# Ampli_FI_10_7MHz.net
KiCad netlist of a schematic drawn in Altium Designer
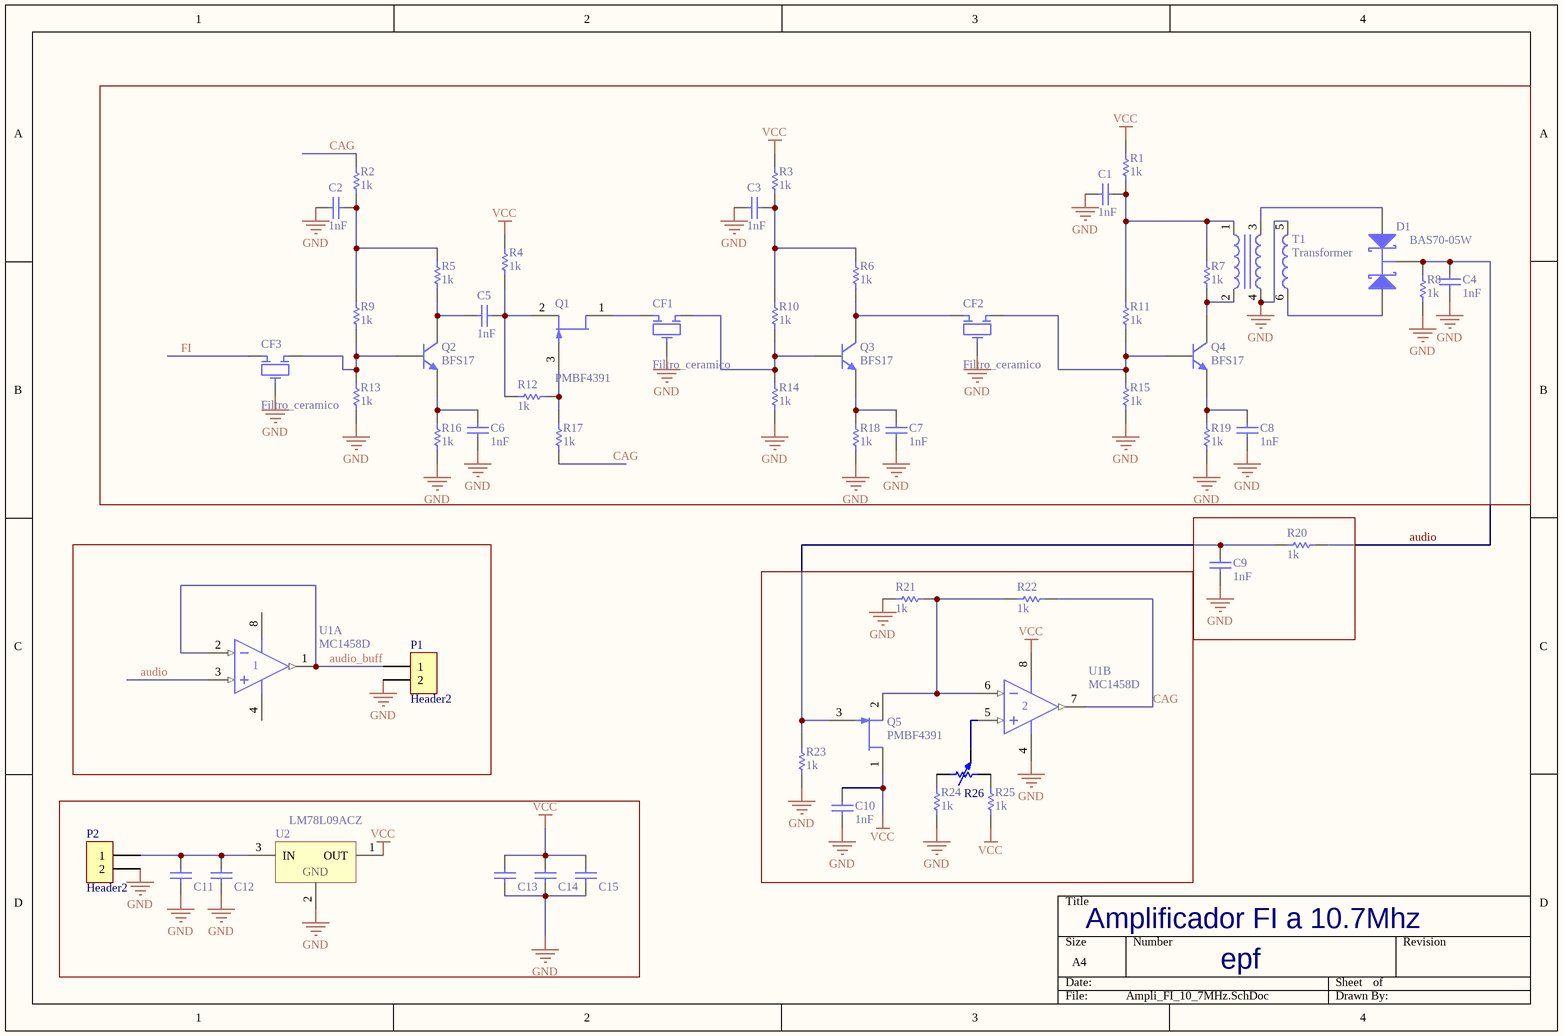
[diagram p0: Ampli_FI_10_7MHz.SchDoc]

(export (version "E")
  (design (tool "Eeschema 10.0.6"))
  (components
    (comp (ref "C1")
      (value "1nF")
      (footprint "0805_CAP")
      (fields (field (name "Comment") "Capacitor"))
      (libsource (lib "epf") (part "Cap"))
    )
    (comp (ref "C2")
      (value "1nF")
      (footprint "0805_CAP")
      (fields (field (name "Comment") "Capacitor"))
      (libsource (lib "epf") (part "Cap"))
    )
    (comp (ref "C3")
      (value "1nF")
      (footprint "0805_CAP")
      (fields (field (name "Comment") "Capacitor"))
      (libsource (lib "epf") (part "Cap"))
    )
    (comp (ref "C4")
      (value "1nF")
      (footprint "0805_CAP")
      (fields (field (name "Comment") "Capacitor"))
      (libsource (lib "epf") (part "Cap"))
    )
    (comp (ref "C5")
      (value "1nF")
      (footprint "0805_CAP")
      (fields (field (name "Comment") "Capacitor"))
      (libsource (lib "epf") (part "Cap"))
    )
    (comp (ref "C6")
      (value "1nF")
      (footprint "0805_CAP")
      (fields (field (name "Comment") "Capacitor"))
      (libsource (lib "epf") (part "Cap"))
    )
    (comp (ref "C7")
      (value "1nF")
      (footprint "0805_CAP")
      (fields (field (name "Comment") "Capacitor"))
      (libsource (lib "epf") (part "Cap"))
    )
    (comp (ref "C8")
      (value "1nF")
      (footprint "0805_CAP")
      (fields (field (name "Comment") "Capacitor"))
      (libsource (lib "epf") (part "Cap"))
    )
    (comp (ref "C9")
      (value "1nF")
      (footprint "0805_CAP")
      (fields (field (name "Comment") "Capacitor"))
      (libsource (lib "epf") (part "Cap"))
    )
    (comp (ref "C10")
      (value "1nF")
      (footprint "0805_CAP")
      (fields (field (name "Comment") "Capacitor"))
      (libsource (lib "epf") (part "Cap"))
    )
    (comp (ref "C11") (value "Capacitor") (footprint "0805_CAP") (libsource (lib "epf") (part "Cap")))
    (comp (ref "C12") (value "Capacitor") (footprint "0805_CAP") (libsource (lib "epf") (part "Cap")))
    (comp (ref "C13") (value "Capacitor") (footprint "0805_CAP") (libsource (lib "epf") (part "Cap")))
    (comp (ref "C14") (value "Capacitor") (footprint "0805_CAP") (libsource (lib "epf") (part "Cap")))
    (comp (ref "C15") (value "Capacitor") (footprint "0805_CAP") (libsource (lib "epf") (part "Cap")))
    (comp (ref "CF1")
      (value "Filtro_ceramico")
      (footprint "Filter_10_7")
      (libsource (lib "epf") (part "Filter_10_7"))
    )
    (comp (ref "CF2")
      (value "Filtro_ceramico")
      (footprint "Filter_10_7")
      (libsource (lib "epf") (part "Filter_10_7"))
    )
    (comp (ref "CF3")
      (value "Filtro_ceramico")
      (footprint "Filter_10_7")
      (libsource (lib "epf") (part "Filter_10_7"))
    )
    (comp (ref "D1")
      (value "BAS70-05W")
      (footprint "SOT323_N")
      (description "Schottky Barrier Double Diode")
      (fields (field (name "PUBLISHER") "Altium Limited"))
      (libsource (lib "Philips Discrete Diode - Schottky") (part "BAS70-05W"))
    )
    (comp (ref "P1") (value "Header2") (footprint "Header2Macho") (libsource (lib "") (part "Header2_1")))
    (comp (ref "P2") (value "Header2") (footprint "Header2Hembra") (libsource (lib "epf") (part "Header2")))
    (comp (ref "Q1")
      (value "PMBF4391")
      (footprint "SOT23")
      (description "N-channel Silicon Junction Field-effect Transistor")
      (fields (field (name "PUBLISHER") "Altium Limited"))
      (libsource (lib "") (part "PMBF4391_1"))
    )
    (comp (ref "Q2")
      (value "BFS17")
      (footprint "SOT23")
      (description "NPN 1 GHz Wideband Transistor")
      (fields (field (name "PUBLISHER") "Altium Limited"))
      (libsource (lib "epf") (part "BFS17"))
    )
    (comp (ref "Q3")
      (value "BFS17")
      (footprint "SOT23")
      (description "NPN 1 GHz Wideband Transistor")
      (fields (field (name "PUBLISHER") "Altium Limited"))
      (libsource (lib "epf") (part "BFS17"))
    )
    (comp (ref "Q4")
      (value "BFS17")
      (footprint "SOT23")
      (description "NPN 1 GHz Wideband Transistor")
      (fields (field (name "PUBLISHER") "Altium Limited"))
      (libsource (lib "epf") (part "BFS17"))
    )
    (comp (ref "Q5")
      (value "PMBF4391")
      (footprint "SOT23")
      (description "N-channel Silicon Junction Field-effect Transistor")
      (fields (field (name "PUBLISHER") "Altium Limited"))
      (libsource (lib "Philips Discrete JFET") (part "PMBF4391"))
    )
    (comp (ref "R1")
      (value "1k")
      (footprint "0805_RES")
      (fields (field (name "Comment") "Resistor"))
      (libsource (lib "epf") (part "Res"))
    )
    (comp (ref "R2")
      (value "1k")
      (footprint "0805_RES")
      (fields (field (name "Comment") "Resistor"))
      (libsource (lib "epf") (part "Res"))
    )
    (comp (ref "R3")
      (value "1k")
      (footprint "0805_RES")
      (fields (field (name "Comment") "Resistor"))
      (libsource (lib "epf") (part "Res"))
    )
    (comp (ref "R4")
      (value "1k")
      (footprint "0805_RES")
      (fields (field (name "Comment") "Resistor"))
      (libsource (lib "epf") (part "Res"))
    )
    (comp (ref "R5")
      (value "1k")
      (footprint "0805_RES")
      (fields (field (name "Comment") "Resistor"))
      (libsource (lib "epf") (part "Res"))
    )
    (comp (ref "R6")
      (value "1k")
      (footprint "0805_RES")
      (fields (field (name "Comment") "Resistor"))
      (libsource (lib "epf") (part "Res"))
    )
    (comp (ref "R7")
      (value "1k")
      (footprint "0805_RES")
      (fields (field (name "Comment") "Resistor"))
      (libsource (lib "epf") (part "Res"))
    )
    (comp (ref "R8")
      (value "1k")
      (footprint "0805_RES")
      (fields (field (name "Comment") "Resistor"))
      (libsource (lib "epf") (part "Res"))
    )
    (comp (ref "R9")
      (value "1k")
      (footprint "0805_RES")
      (fields (field (name "Comment") "Resistor"))
      (libsource (lib "epf") (part "Res"))
    )
    (comp (ref "R10")
      (value "1k")
      (footprint "0805_RES")
      (fields (field (name "Comment") "Resistor"))
      (libsource (lib "epf") (part "Res"))
    )
    (comp (ref "R11")
      (value "1k")
      (footprint "0805_RES")
      (fields (field (name "Comment") "Resistor"))
      (libsource (lib "epf") (part "Res"))
    )
    (comp (ref "R12")
      (value "1k")
      (footprint "0805_RES")
      (fields (field (name "Comment") "Resistor"))
      (libsource (lib "epf") (part "Res"))
    )
    (comp (ref "R13")
      (value "1k")
      (footprint "0805_RES")
      (fields (field (name "Comment") "Resistor"))
      (libsource (lib "epf") (part "Res"))
    )
    (comp (ref "R14")
      (value "1k")
      (footprint "0805_RES")
      (fields (field (name "Comment") "Resistor"))
      (libsource (lib "epf") (part "Res"))
    )
    (comp (ref "R15")
      (value "1k")
      (footprint "0805_RES")
      (fields (field (name "Comment") "Resistor"))
      (libsource (lib "epf") (part "Res"))
    )
    (comp (ref "R16")
      (value "1k")
      (footprint "0805_RES")
      (fields (field (name "Comment") "Resistor"))
      (libsource (lib "epf") (part "Res"))
    )
    (comp (ref "R17")
      (value "1k")
      (footprint "0805_RES")
      (fields (field (name "Comment") "Resistor"))
      (libsource (lib "epf") (part "Res"))
    )
    (comp (ref "R18")
      (value "1k")
      (footprint "0805_RES")
      (fields (field (name "Comment") "Resistor"))
      (libsource (lib "epf") (part "Res"))
    )
    (comp (ref "R19")
      (value "1k")
      (footprint "0805_RES")
      (fields (field (name "Comment") "Resistor"))
      (libsource (lib "epf") (part "Res"))
    )
    (comp (ref "R20")
      (value "1k")
      (footprint "0805_RES")
      (fields (field (name "Comment") "Resistor"))
      (libsource (lib "epf") (part "Res"))
    )
    (comp (ref "R21")
      (value "1k")
      (footprint "0805_RES")
      (fields (field (name "Comment") "Resistor"))
      (libsource (lib "epf") (part "Res"))
    )
    (comp (ref "R22")
      (value "1k")
      (footprint "0805_RES")
      (fields (field (name "Comment") "Resistor"))
      (libsource (lib "epf") (part "Res"))
    )
    (comp (ref "R23")
      (value "1k")
      (footprint "0805_RES")
      (fields (field (name "Comment") "Resistor"))
      (libsource (lib "epf") (part "Res"))
    )
    (comp (ref "R24")
      (value "1k")
      (footprint "0805_RES")
      (fields (field (name "Comment") "Resistor"))
      (libsource (lib "epf") (part "Res"))
    )
    (comp (ref "R25")
      (value "1k")
      (footprint "0805_RES")
      (fields (field (name "Comment") "Resistor"))
      (libsource (lib "epf") (part "Res"))
    )
    (comp (ref "R26") (value "Pot") (footprint "POT_SMD") (libsource (lib "epf") (part "Pot")))
    (comp (ref "T1")
      (value "Transformer")
      (footprint "NTH12_V_3Ind_2")
      (description "Transformador 3 bobinas")
      (libsource (lib "epf") (part "Transformador3"))
    )
    (comp (ref "U1")
      (value "MC1458D")
      (footprint "SO-8_2")
      (description "Dual Operational Amplifier, Internally Compensated")
      (fields (field (name "PUBLISHER") "Altium Limited"))
      (libsource (lib "Motorola Amplifier Operational Amplifier") (part "MC1458D"))
    )
    (comp (ref "U2")
      (value "LM78L09ACZ")
      (footprint "TO92")
      (description "3-Terminal Positive Regulators")
      (fields
        (field (name "MANUFACTURER") "National Semiconductor")
        (field (name "DIGIKEYPARTNUMBER") "LM78L09ACZ-ND")
        (field (name "PUBLISHER") "Altium Limited")
      )
      (libsource (lib "NSC LDO") (part "LM78L09ACZ"))
    )
  )
  (nets
    (net (code "1") (name "/CAG") (class "Default")
      (node (ref "R17") (pin "2") (pinfunction "2_2") (pintype "passive"))
      (node (ref "R2") (pin "1") (pinfunction "1_1") (pintype "passive"))
      (node (ref "R22") (pin "2") (pinfunction "2_2") (pintype "passive"))
      (node (ref "U1") (pin "7") (pinfunction "OUT_7") (pintype "output"))
    )
    (net (code "2") (name "/FI") (class "Default")
      (node (ref "CF3") (pin "1") (pinfunction "1_1") (pintype "passive"))
    )
    (net (code "3") (name "/audio") (class "Default")
      (node (ref "C4") (pin "2") (pinfunction "2_2") (pintype "passive"))
      (node (ref "D1") (pin "3") (pinfunction "K_3") (pintype "passive"))
      (node (ref "R20") (pin "2") (pinfunction "2_2") (pintype "passive"))
      (node (ref "R8") (pin "1") (pinfunction "1_1") (pintype "passive"))
      (node (ref "U1") (pin "3") (pinfunction "IN+_3") (pintype "input"))
    )
    (net (code "4") (name "/audio_buff") (class "Default")
      (node (ref "P1") (pin "1") (pinfunction "1_1") (pintype "passive"))
      (node (ref "U1") (pin "1") (pinfunction "OUT_1") (pintype "output"))
      (node (ref "U1") (pin "2") (pinfunction "IN-_2") (pintype "input"))
    )
    (net (code "5") (name "GND") (class "Default")
      (node (ref "C1") (pin "1") (pinfunction "1_1") (pintype "passive"))
      (node (ref "C10") (pin "1") (pinfunction "1_1") (pintype "passive"))
      (node (ref "C11") (pin "1") (pinfunction "1_1") (pintype "passive"))
      (node (ref "C12") (pin "1") (pinfunction "1_1") (pintype "passive"))
      (node (ref "C13") (pin "1") (pinfunction "1_1") (pintype "passive"))
      (node (ref "C14") (pin "1") (pinfunction "1_1") (pintype "passive"))
      (node (ref "C15") (pin "1") (pinfunction "1_1") (pintype "passive"))
      (node (ref "C2") (pin "2") (pinfunction "2_2") (pintype "passive"))
      (node (ref "C3") (pin "2") (pinfunction "2_2") (pintype "passive"))
      (node (ref "C4") (pin "1") (pinfunction "1_1") (pintype "passive"))
      (node (ref "C6") (pin "2") (pinfunction "2_2") (pintype "passive"))
      (node (ref "C7") (pin "2") (pinfunction "2_2") (pintype "passive"))
      (node (ref "C8") (pin "1") (pinfunction "1_1") (pintype "passive"))
      (node (ref "C9") (pin "1") (pinfunction "1_1") (pintype "passive"))
      (node (ref "CF1") (pin "2") (pinfunction "2_2") (pintype "passive"))
      (node (ref "CF2") (pin "2") (pinfunction "2_2") (pintype "passive"))
      (node (ref "CF3") (pin "2") (pinfunction "2_2") (pintype "passive"))
      (node (ref "P1") (pin "2") (pinfunction "2_2") (pintype "passive"))
      (node (ref "P2") (pin "2") (pinfunction "2_2") (pintype "passive"))
      (node (ref "R13") (pin "2") (pinfunction "2_2") (pintype "passive"))
      (node (ref "R14") (pin "2") (pinfunction "2_2") (pintype "passive"))
      (node (ref "R15") (pin "2") (pinfunction "2_2") (pintype "passive"))
      (node (ref "R16") (pin "2") (pinfunction "2_2") (pintype "passive"))
      (node (ref "R18") (pin "2") (pinfunction "2_2") (pintype "passive"))
      (node (ref "R19") (pin "2") (pinfunction "2_2") (pintype "passive"))
      (node (ref "R21") (pin "1") (pinfunction "1_1") (pintype "passive"))
      (node (ref "R23") (pin "2") (pinfunction "2_2") (pintype "passive"))
      (node (ref "R24") (pin "2") (pinfunction "2_2") (pintype "passive"))
      (node (ref "R8") (pin "2") (pinfunction "2_2") (pintype "passive"))
      (node (ref "T1") (pin "4") (pinfunction "4_4") (pintype "passive"))
      (node (ref "T1") (pin "5") (pinfunction "5_5") (pintype "passive"))
      (node (ref "U1") (pin "4") (pinfunction "V-_4") (pintype "power_in"))
      (node (ref "U2") (pin "2") (pinfunction "GND_2") (pintype "power_in"))
    )
    (net (code "6") (name "Net-(C1-Pad2)") (class "Default")
      (node (ref "C1") (pin "2") (pinfunction "2_2") (pintype "passive"))
      (node (ref "R1") (pin "2") (pinfunction "2_2") (pintype "passive"))
      (node (ref "R11") (pin "1") (pinfunction "1_1") (pintype "passive"))
      (node (ref "R7") (pin "1") (pinfunction "1_1") (pintype "passive"))
      (node (ref "T1") (pin "1") (pinfunction "1_1") (pintype "passive"))
    )
    (net (code "7") (name "Net-(C2-Pad1)") (class "Default")
      (node (ref "C2") (pin "1") (pinfunction "1_1") (pintype "passive"))
      (node (ref "R2") (pin "2") (pinfunction "2_2") (pintype "passive"))
      (node (ref "R5") (pin "1") (pinfunction "1_1") (pintype "passive"))
      (node (ref "R9") (pin "1") (pinfunction "1_1") (pintype "passive"))
    )
    (net (code "8") (name "Net-(C3-Pad1)") (class "Default")
      (node (ref "C3") (pin "1") (pinfunction "1_1") (pintype "passive"))
      (node (ref "R10") (pin "1") (pinfunction "1_1") (pintype "passive"))
      (node (ref "R3") (pin "2") (pinfunction "2_2") (pintype "passive"))
      (node (ref "R6") (pin "1") (pinfunction "1_1") (pintype "passive"))
    )
    (net (code "9") (name "Net-(D1-A1)") (class "Default")
      (node (ref "D1") (pin "1") (pinfunction "A1_1") (pintype "passive"))
      (node (ref "T1") (pin "3") (pinfunction "3_3") (pintype "passive"))
    )
    (net (code "10") (name "Net-(D1-A2)") (class "Default")
      (node (ref "D1") (pin "2") (pinfunction "A2_2") (pintype "passive"))
      (node (ref "T1") (pin "6") (pinfunction "6_6") (pintype "passive"))
    )
    (net (code "11") (name "Net-(Q1-D)") (class "Default")
      (node (ref "CF1") (pin "1") (pinfunction "1_1") (pintype "passive"))
      (node (ref "Q1") (pin "1") (pinfunction "D_1") (pintype "passive"))
    )
    (net (code "12") (name "Net-(Q1-G)") (class "Default")
      (node (ref "Q1") (pin "3") (pinfunction "G_3") (pintype "passive"))
      (node (ref "R12") (pin "2") (pinfunction "2_2") (pintype "passive"))
      (node (ref "R17") (pin "1") (pinfunction "1_1") (pintype "passive"))
    )
    (net (code "13") (name "Net-(Q1-S)") (class "Default")
      (node (ref "C5") (pin "1") (pinfunction "1_1") (pintype "passive"))
      (node (ref "Q1") (pin "2") (pinfunction "S_2") (pintype "passive"))
      (node (ref "R12") (pin "1") (pinfunction "1_1") (pintype "passive"))
      (node (ref "R4") (pin "2") (pinfunction "2_2") (pintype "passive"))
    )
    (net (code "14") (name "Net-(Q2-B)") (class "Default")
      (node (ref "CF3") (pin "3") (pinfunction "3_3") (pintype "passive"))
      (node (ref "Q2") (pin "1") (pinfunction "B_1") (pintype "passive"))
      (node (ref "R13") (pin "1") (pinfunction "1_1") (pintype "passive"))
      (node (ref "R9") (pin "2") (pinfunction "2_2") (pintype "passive"))
    )
    (net (code "15") (name "Net-(Q2-C)") (class "Default")
      (node (ref "C5") (pin "2") (pinfunction "2_2") (pintype "passive"))
      (node (ref "Q2") (pin "3") (pinfunction "C_3") (pintype "passive"))
      (node (ref "R5") (pin "2") (pinfunction "2_2") (pintype "passive"))
    )
    (net (code "16") (name "Net-(Q2-E)") (class "Default")
      (node (ref "C6") (pin "1") (pinfunction "1_1") (pintype "passive"))
      (node (ref "Q2") (pin "2") (pinfunction "E_2") (pintype "passive"))
      (node (ref "R16") (pin "1") (pinfunction "1_1") (pintype "passive"))
    )
    (net (code "17") (name "Net-(Q3-B)") (class "Default")
      (node (ref "CF1") (pin "3") (pinfunction "3_3") (pintype "passive"))
      (node (ref "Q3") (pin "1") (pinfunction "B_1") (pintype "passive"))
      (node (ref "R10") (pin "2") (pinfunction "2_2") (pintype "passive"))
      (node (ref "R14") (pin "1") (pinfunction "1_1") (pintype "passive"))
    )
    (net (code "18") (name "Net-(Q3-C)") (class "Default")
      (node (ref "CF2") (pin "1") (pinfunction "1_1") (pintype "passive"))
      (node (ref "Q3") (pin "3") (pinfunction "C_3") (pintype "passive"))
      (node (ref "R6") (pin "2") (pinfunction "2_2") (pintype "passive"))
    )
    (net (code "19") (name "Net-(Q3-E)") (class "Default")
      (node (ref "C7") (pin "1") (pinfunction "1_1") (pintype "passive"))
      (node (ref "Q3") (pin "2") (pinfunction "E_2") (pintype "passive"))
      (node (ref "R18") (pin "1") (pinfunction "1_1") (pintype "passive"))
    )
    (net (code "20") (name "Net-(Q4-B)") (class "Default")
      (node (ref "CF2") (pin "3") (pinfunction "3_3") (pintype "passive"))
      (node (ref "Q4") (pin "1") (pinfunction "B_1") (pintype "passive"))
      (node (ref "R11") (pin "2") (pinfunction "2_2") (pintype "passive"))
      (node (ref "R15") (pin "1") (pinfunction "1_1") (pintype "passive"))
    )
    (net (code "21") (name "Net-(Q4-C)") (class "Default")
      (node (ref "Q4") (pin "3") (pinfunction "C_3") (pintype "passive"))
      (node (ref "R7") (pin "2") (pinfunction "2_2") (pintype "passive"))
      (node (ref "T1") (pin "2") (pinfunction "2_2") (pintype "passive"))
    )
    (net (code "22") (name "Net-(Q4-E)") (class "Default")
      (node (ref "C8") (pin "2") (pinfunction "2_2") (pintype "passive"))
      (node (ref "Q4") (pin "2") (pinfunction "E_2") (pintype "passive"))
      (node (ref "R19") (pin "1") (pinfunction "1_1") (pintype "passive"))
    )
    (net (code "23") (name "Net-(Q5-G)") (class "Default")
      (node (ref "C9") (pin "2") (pinfunction "2_2") (pintype "passive"))
      (node (ref "Q5") (pin "3") (pinfunction "G_3") (pintype "passive"))
      (node (ref "R20") (pin "1") (pinfunction "1_1") (pintype "passive"))
      (node (ref "R23") (pin "1") (pinfunction "1_1") (pintype "passive"))
    )
    (net (code "24") (name "Net-(Q5-S)") (class "Default")
      (node (ref "Q5") (pin "2") (pinfunction "S_2") (pintype "passive"))
      (node (ref "R21") (pin "2") (pinfunction "2_2") (pintype "passive"))
      (node (ref "R22") (pin "1") (pinfunction "1_1") (pintype "passive"))
      (node (ref "U1") (pin "6") (pinfunction "IN-_6") (pintype "input"))
    )
    (net (code "25") (name "Net-(R24-Pad1)") (class "Default")
      (node (ref "R24") (pin "1") (pinfunction "1_1") (pintype "passive"))
      (node (ref "R26") (pin "1") (pinfunction "1_1") (pintype "passive"))
    )
    (net (code "26") (name "Net-(R25-Pad2)") (class "Default")
      (node (ref "R25") (pin "2") (pinfunction "2_2") (pintype "passive"))
      (node (ref "R26") (pin "2") (pinfunction "2_2") (pintype "passive"))
    )
    (net (code "27") (name "Net-(U1B-IN+)") (class "Default")
      (node (ref "R26") (pin "3") (pinfunction "3_3") (pintype "passive"))
      (node (ref "U1") (pin "5") (pinfunction "IN+_5") (pintype "input"))
    )
    (net (code "28") (name "Net-(U2-IN)") (class "Default")
      (node (ref "C11") (pin "2") (pinfunction "2_2") (pintype "passive"))
      (node (ref "C12") (pin "2") (pinfunction "2_2") (pintype "passive"))
      (node (ref "P2") (pin "1") (pinfunction "1_1") (pintype "passive"))
      (node (ref "U2") (pin "3") (pinfunction "IN_3") (pintype "power_in"))
    )
    (net (code "29") (name "VCC") (class "Default")
      (node (ref "C10") (pin "2") (pinfunction "2_2") (pintype "passive"))
      (node (ref "C13") (pin "2") (pinfunction "2_2") (pintype "passive"))
      (node (ref "C14") (pin "2") (pinfunction "2_2") (pintype "passive"))
      (node (ref "C15") (pin "2") (pinfunction "2_2") (pintype "passive"))
      (node (ref "Q5") (pin "1") (pinfunction "D_1") (pintype "passive"))
      (node (ref "R1") (pin "1") (pinfunction "1_1") (pintype "passive"))
      (node (ref "R25") (pin "1") (pinfunction "1_1") (pintype "passive"))
      (node (ref "R3") (pin "1") (pinfunction "1_1") (pintype "passive"))
      (node (ref "R4") (pin "1") (pinfunction "1_1") (pintype "passive"))
      (node (ref "U1") (pin "8") (pinfunction "V+_8") (pintype "power_in"))
      (node (ref "U2") (pin "1") (pinfunction "OUT_1") (pintype "power_in"))
    )
    (net (code "30") (name "unconnected-(U1A-V+-Pad8)") (class "Default")
      (node (ref "U1") (pin "8") (pinfunction "V+_8") (pintype "power_in"))
    )
    (net (code "31") (name "unconnected-(U1A-V--Pad4)") (class "Default")
      (node (ref "U1") (pin "4") (pinfunction "V-_4") (pintype "power_in"))
    )
  )
)
